# joil.net
KiCad netlist of a schematic drawn in EasyEDA Pro
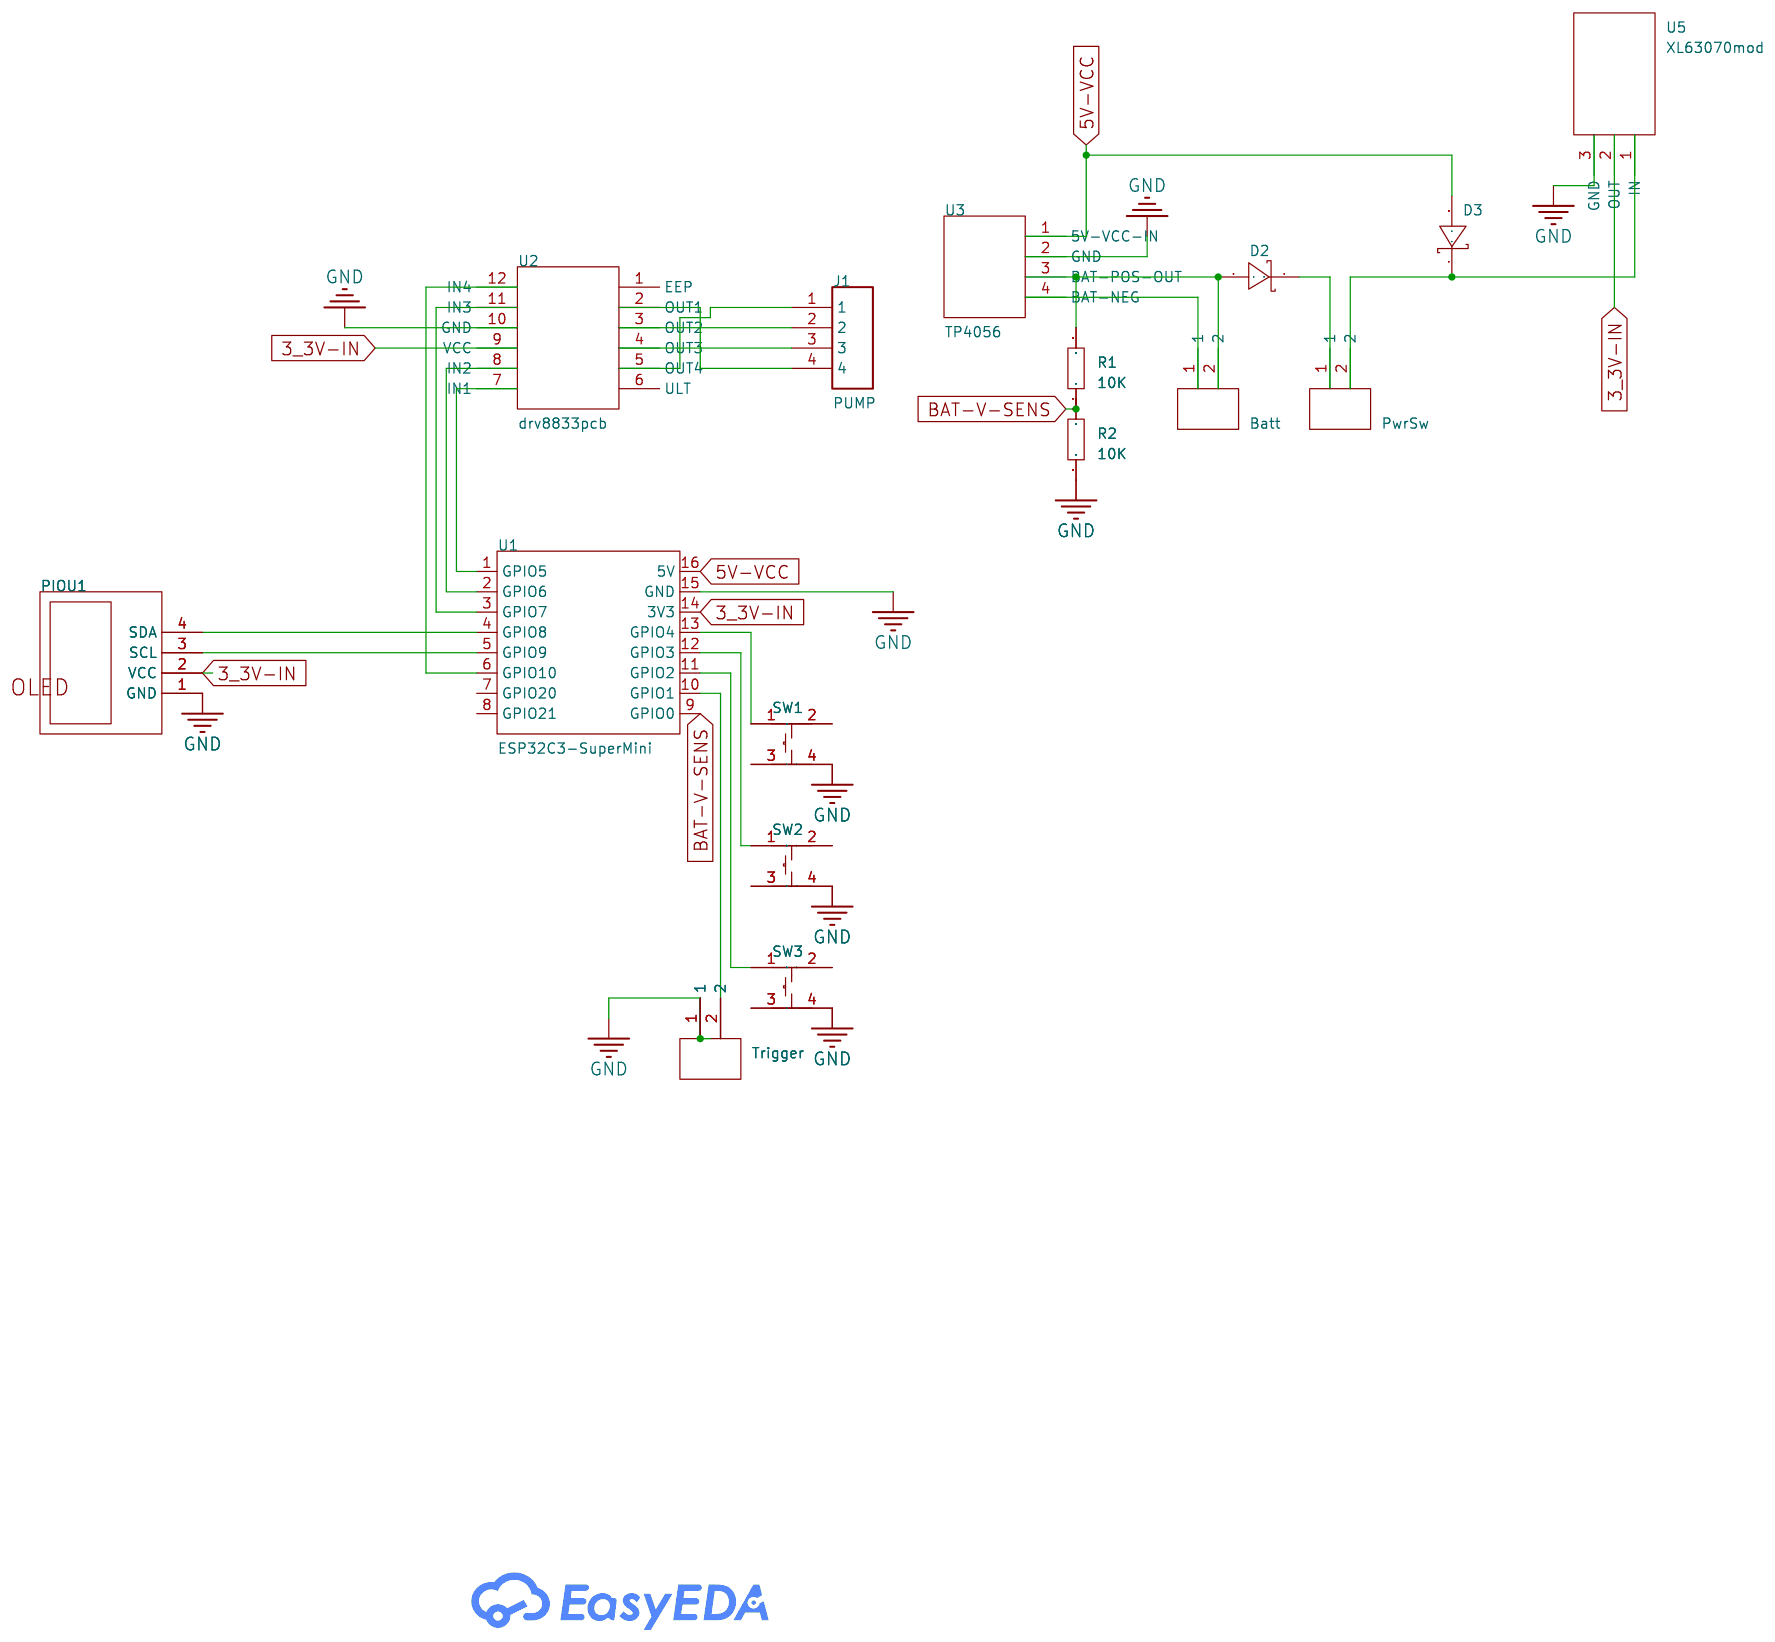
[diagram p0: schematic sheet]

(export (version "E")
  (design (tool "Eeschema 10.0.6"))
  (components
    (comp (ref "Batt")
      (value "Batt")
      (footprint "easyedapro:jst2pin")
      (libsource (lib "easyedapro") (part "jst2pin"))
    )
    (comp (ref "D2")
      (value "SS14")
      (footprint "easyedapro:SMA_L4.2-W2.6-LS5.3-RD")
      (fields (field (name "Manufacturer") "MDD"))
      (libsource (lib "easyedapro") (part "SS14"))
    )
    (comp (ref "D3")
      (value "SS14")
      (footprint "easyedapro:SMA_L4.2-W2.6-LS5.3-RD")
      (fields (field (name "Manufacturer") "MDD"))
      (libsource (lib "easyedapro") (part "SS14"))
    )
    (comp (ref "J1")
      (value "PUMP")
      (footprint "easyedapro:SMD-JST-SH1.0-04PIN-VERTICAL")
      (libsource (lib "easyedapro") (part "JST-SH1.0-04PIN"))
    )
    (comp (ref "PIOU1")
      (value "GRINNAN_OLED 128X64 0,96\" I2C 4PIN")
      (footprint "easyedapro:I2C - OLED 0.96\" 128X64")
      (fields (field (name "Manufacturer Part") "SSD1306 I2C OLED"))
      (libsource (lib "easyedapro") (part "GRINNAN_OLED 128X64 0,96&quot; I2C 4PIN"))
    )
    (comp (ref "PwrSw")
      (value "PwrSw")
      (footprint "easyedapro:jst2pin")
      (libsource (lib "easyedapro") (part "jst2pin"))
    )
    (comp (ref "R1") (value "10K") (footprint "easyedapro:R0603") (libsource (lib "easyedapro") (part "Res")))
    (comp (ref "R2") (value "10K") (footprint "easyedapro:R0603") (libsource (lib "easyedapro") (part "Res")))
    (comp (ref "SW1")
      (value "1TS005F-2500-5001")
      (footprint "easyedapro:KEY-SMD_4P-L6.0-W6.0-P4.50-LS9.0")
      (libsource (lib "easyedapro") (part "1TS005F-2500-5001_C508476"))
    )
    (comp (ref "SW2")
      (value "1TS005F-2500-5001")
      (footprint "easyedapro:KEY-SMD_4P-L6.0-W6.0-P4.50-LS9.0")
      (libsource (lib "easyedapro") (part "1TS005F-2500-5001_C508476"))
    )
    (comp (ref "SW3")
      (value "1TS005F-2500-5001")
      (footprint "easyedapro:KEY-SMD_4P-L6.0-W6.0-P4.50-LS9.0")
      (libsource (lib "easyedapro") (part "1TS005F-2500-5001_C508476"))
    )
    (comp (ref "Trigger")
      (value "Trigger")
      (footprint "easyedapro:jst2pin")
      (libsource (lib "easyedapro") (part "jst2pin"))
    )
    (comp (ref "U1")
      (value "ESP32C3-SuperMini")
      (footprint "easyedapro:COMM-SMD_16P-L22.5-W18.0-P2.54-TL")
      (libsource (lib "easyedapro") (part "ESP32C3-SUPERMINI"))
    )
    (comp (ref "U2") (value "drv8833pcb") (libsource (lib "easyedapro") (part "drv8833pcb")))
    (comp (ref "U3")
      (value "TP4056")
      (footprint "easyedapro:pwr")
      (libsource (lib "easyedapro") (part "pwr"))
    )
    (comp (ref "U5")
      (value "XL63070mod")
      (footprint "easyedapro:XL63070mod")
      (libsource (lib "easyedapro") (part "XL63070mod"))
    )
  )
  (nets
    (net (code "1") (name "3_3V-IN") (class "Default")
      (node (ref "PIOU1") (pin "2") (pinfunction "VCC_2") (pintype "unspecified"))
      (node (ref "U1") (pin "14") (pinfunction "3V3_14") (pintype "unspecified"))
      (node (ref "U2") (pin "9") (pinfunction "VCC_9") (pintype "input"))
      (node (ref "U5") (pin "2") (pinfunction "OUT_2") (pintype "input"))
    )
    (net (code "2") (name "5V-VCC") (class "Default")
      (node (ref "D3") (pin "2") (pinfunction "A_2") (pintype "input"))
      (node (ref "U1") (pin "16") (pinfunction "5V_16") (pintype "unspecified"))
      (node (ref "U3") (pin "1") (pinfunction "5V-VCC-IN_1") (pintype "input"))
    )
    (net (code "3") (name "BAT-V-SENS") (class "Default")
      (node (ref "R1") (pin "1") (pinfunction "1_1") (pintype "input"))
      (node (ref "R2") (pin "2") (pinfunction "2_2") (pintype "input"))
      (node (ref "U1") (pin "9") (pinfunction "GPIO0_9") (pintype "unspecified"))
    )
    (net (code "4") (name "GND") (class "Default")
      (node (ref "PIOU1") (pin "1") (pinfunction "GND_1") (pintype "unspecified"))
      (node (ref "R2") (pin "1") (pinfunction "1_1") (pintype "input"))
      (node (ref "SW1") (pin "4") (pinfunction "4_4") (pintype "unspecified"))
      (node (ref "SW2") (pin "4") (pinfunction "4_4") (pintype "unspecified"))
      (node (ref "SW3") (pin "4") (pinfunction "4_4") (pintype "unspecified"))
      (node (ref "Trigger") (pin "1") (pinfunction "1_1") (pintype "input"))
      (node (ref "U1") (pin "15") (pinfunction "GND_15") (pintype "unspecified"))
      (node (ref "U2") (pin "10") (pinfunction "GND_10") (pintype "input"))
      (node (ref "U3") (pin "2") (pinfunction "GND_2") (pintype "input"))
      (node (ref "U5") (pin "3") (pinfunction "GND_3") (pintype "input"))
    )
    (net (code "5") (name "Net-(D2-A)") (class "Default")
      (node (ref "Batt") (pin "2") (pinfunction "2_2") (pintype "input"))
      (node (ref "D2") (pin "2") (pinfunction "A_2") (pintype "input"))
      (node (ref "R1") (pin "2") (pinfunction "2_2") (pintype "input"))
      (node (ref "U3") (pin "3") (pinfunction "BAT-POS-OUT_3") (pintype "input"))
    )
    (net (code "6") (name "Net-(D2-K)") (class "Default")
      (node (ref "D2") (pin "1") (pinfunction "K_1") (pintype "input"))
      (node (ref "PwrSw") (pin "1") (pinfunction "1_1") (pintype "input"))
    )
    (net (code "7") (name "Net-(D3-K)") (class "Default")
      (node (ref "D3") (pin "1") (pinfunction "K_1") (pintype "input"))
      (node (ref "PwrSw") (pin "2") (pinfunction "2_2") (pintype "input"))
      (node (ref "U5") (pin "1") (pinfunction "IN_1") (pintype "input"))
    )
    (net (code "8") (name "Net-(PIOU1-SCL)") (class "Default")
      (node (ref "PIOU1") (pin "3") (pinfunction "SCL_3") (pintype "unspecified"))
      (node (ref "U1") (pin "5") (pinfunction "GPIO9_5") (pintype "unspecified"))
    )
    (net (code "9") (name "Net-(PIOU1-SDA)") (class "Default")
      (node (ref "PIOU1") (pin "4") (pinfunction "SDA_4") (pintype "unspecified"))
      (node (ref "U1") (pin "4") (pinfunction "GPIO8_4") (pintype "unspecified"))
    )
    (net (code "10") (name "Net-(U1-GPIO1)") (class "Default")
      (node (ref "Trigger") (pin "2") (pinfunction "2_2") (pintype "input"))
      (node (ref "U1") (pin "10") (pinfunction "GPIO1_10") (pintype "unspecified"))
    )
    (net (code "11") (name "Net-(U1-GPIO2)") (class "Default")
      (node (ref "SW3") (pin "1") (pinfunction "1_1") (pintype "unspecified"))
      (node (ref "U1") (pin "11") (pinfunction "GPIO2_11") (pintype "unspecified"))
    )
    (net (code "12") (name "Net-(U1-GPIO3)") (class "Default")
      (node (ref "SW2") (pin "1") (pinfunction "1_1") (pintype "unspecified"))
      (node (ref "U1") (pin "12") (pinfunction "GPIO3_12") (pintype "unspecified"))
    )
    (net (code "13") (name "Net-(U1-GPIO4)") (class "Default")
      (node (ref "SW1") (pin "1") (pinfunction "1_1") (pintype "unspecified"))
      (node (ref "U1") (pin "13") (pinfunction "GPIO4_13") (pintype "unspecified"))
    )
    (net (code "14") (name "Net-(U1-GPIO5)") (class "Default")
      (node (ref "U1") (pin "1") (pinfunction "GPIO5_1") (pintype "unspecified"))
      (node (ref "U2") (pin "7") (pinfunction "IN1_7") (pintype "input"))
    )
    (net (code "15") (name "Net-(U1-GPIO6)") (class "Default")
      (node (ref "U1") (pin "2") (pinfunction "GPIO6_2") (pintype "unspecified"))
      (node (ref "U2") (pin "8") (pinfunction "IN2_8") (pintype "input"))
    )
    (net (code "16") (name "Net-(U1-GPIO7)") (class "Default")
      (node (ref "U1") (pin "3") (pinfunction "GPIO7_3") (pintype "unspecified"))
      (node (ref "U2") (pin "11") (pinfunction "IN3_11") (pintype "input"))
    )
    (net (code "17") (name "Net-(U1-GPIO10)") (class "Default")
      (node (ref "U1") (pin "6") (pinfunction "GPIO10_6") (pintype "unspecified"))
      (node (ref "U2") (pin "12") (pinfunction "IN4_12") (pintype "input"))
    )
    (net (code "18") (name "Net-(U2-OUT1)") (class "Default")
      (node (ref "J1") (pin "4") (pinfunction "4_4") (pintype "unspecified"))
      (node (ref "U2") (pin "2") (pinfunction "OUT1_2") (pintype "output"))
    )
    (net (code "19") (name "Net-(U2-OUT2)") (class "Default")
      (node (ref "J1") (pin "2") (pinfunction "2_2") (pintype "unspecified"))
      (node (ref "U2") (pin "3") (pinfunction "OUT2_3") (pintype "output"))
    )
    (net (code "20") (name "Net-(U2-OUT3)") (class "Default")
      (node (ref "J1") (pin "3") (pinfunction "3_3") (pintype "unspecified"))
      (node (ref "U2") (pin "4") (pinfunction "OUT3_4") (pintype "output"))
    )
    (net (code "21") (name "Net-(U2-OUT4)") (class "Default")
      (node (ref "J1") (pin "1") (pinfunction "1_1") (pintype "unspecified"))
      (node (ref "U2") (pin "5") (pinfunction "OUT4_5") (pintype "output"))
    )
    (net (code "22") (name "Net-(U3-BAT-NEG)") (class "Default")
      (node (ref "Batt") (pin "1") (pinfunction "1_1") (pintype "input"))
      (node (ref "U3") (pin "4") (pinfunction "BAT-NEG_4") (pintype "input"))
    )
    (net (code "23") (name "unconnected-(SW1-Pad2)") (class "Default")
      (node (ref "SW1") (pin "2") (pinfunction "2_2") (pintype "unspecified"))
    )
    (net (code "24") (name "unconnected-(SW1-Pad3)") (class "Default")
      (node (ref "SW1") (pin "3") (pinfunction "3_3") (pintype "unspecified"))
    )
    (net (code "25") (name "unconnected-(SW2-Pad2)") (class "Default")
      (node (ref "SW2") (pin "2") (pinfunction "2_2") (pintype "unspecified"))
    )
    (net (code "26") (name "unconnected-(SW2-Pad3)") (class "Default")
      (node (ref "SW2") (pin "3") (pinfunction "3_3") (pintype "unspecified"))
    )
    (net (code "27") (name "unconnected-(SW3-Pad2)") (class "Default")
      (node (ref "SW3") (pin "2") (pinfunction "2_2") (pintype "unspecified"))
    )
    (net (code "28") (name "unconnected-(SW3-Pad3)") (class "Default")
      (node (ref "SW3") (pin "3") (pinfunction "3_3") (pintype "unspecified"))
    )
    (net (code "29") (name "unconnected-(U1-GPIO20-Pad7)") (class "Default")
      (node (ref "U1") (pin "7") (pinfunction "GPIO20_7") (pintype "unspecified"))
    )
    (net (code "30") (name "unconnected-(U1-GPIO21-Pad8)") (class "Default")
      (node (ref "U1") (pin "8") (pinfunction "GPIO21_8") (pintype "unspecified"))
    )
    (net (code "31") (name "unconnected-(U2-EEP-Pad1)") (class "Default")
      (node (ref "U2") (pin "1") (pinfunction "EEP_1") (pintype "input"))
    )
    (net (code "32") (name "unconnected-(U2-ULT-Pad6)") (class "Default")
      (node (ref "U2") (pin "6") (pinfunction "ULT_6") (pintype "output"))
    )
  )
)
